# e-Tapperhandpiece.net
KiCad netlist of a schematic drawn in EAGLE
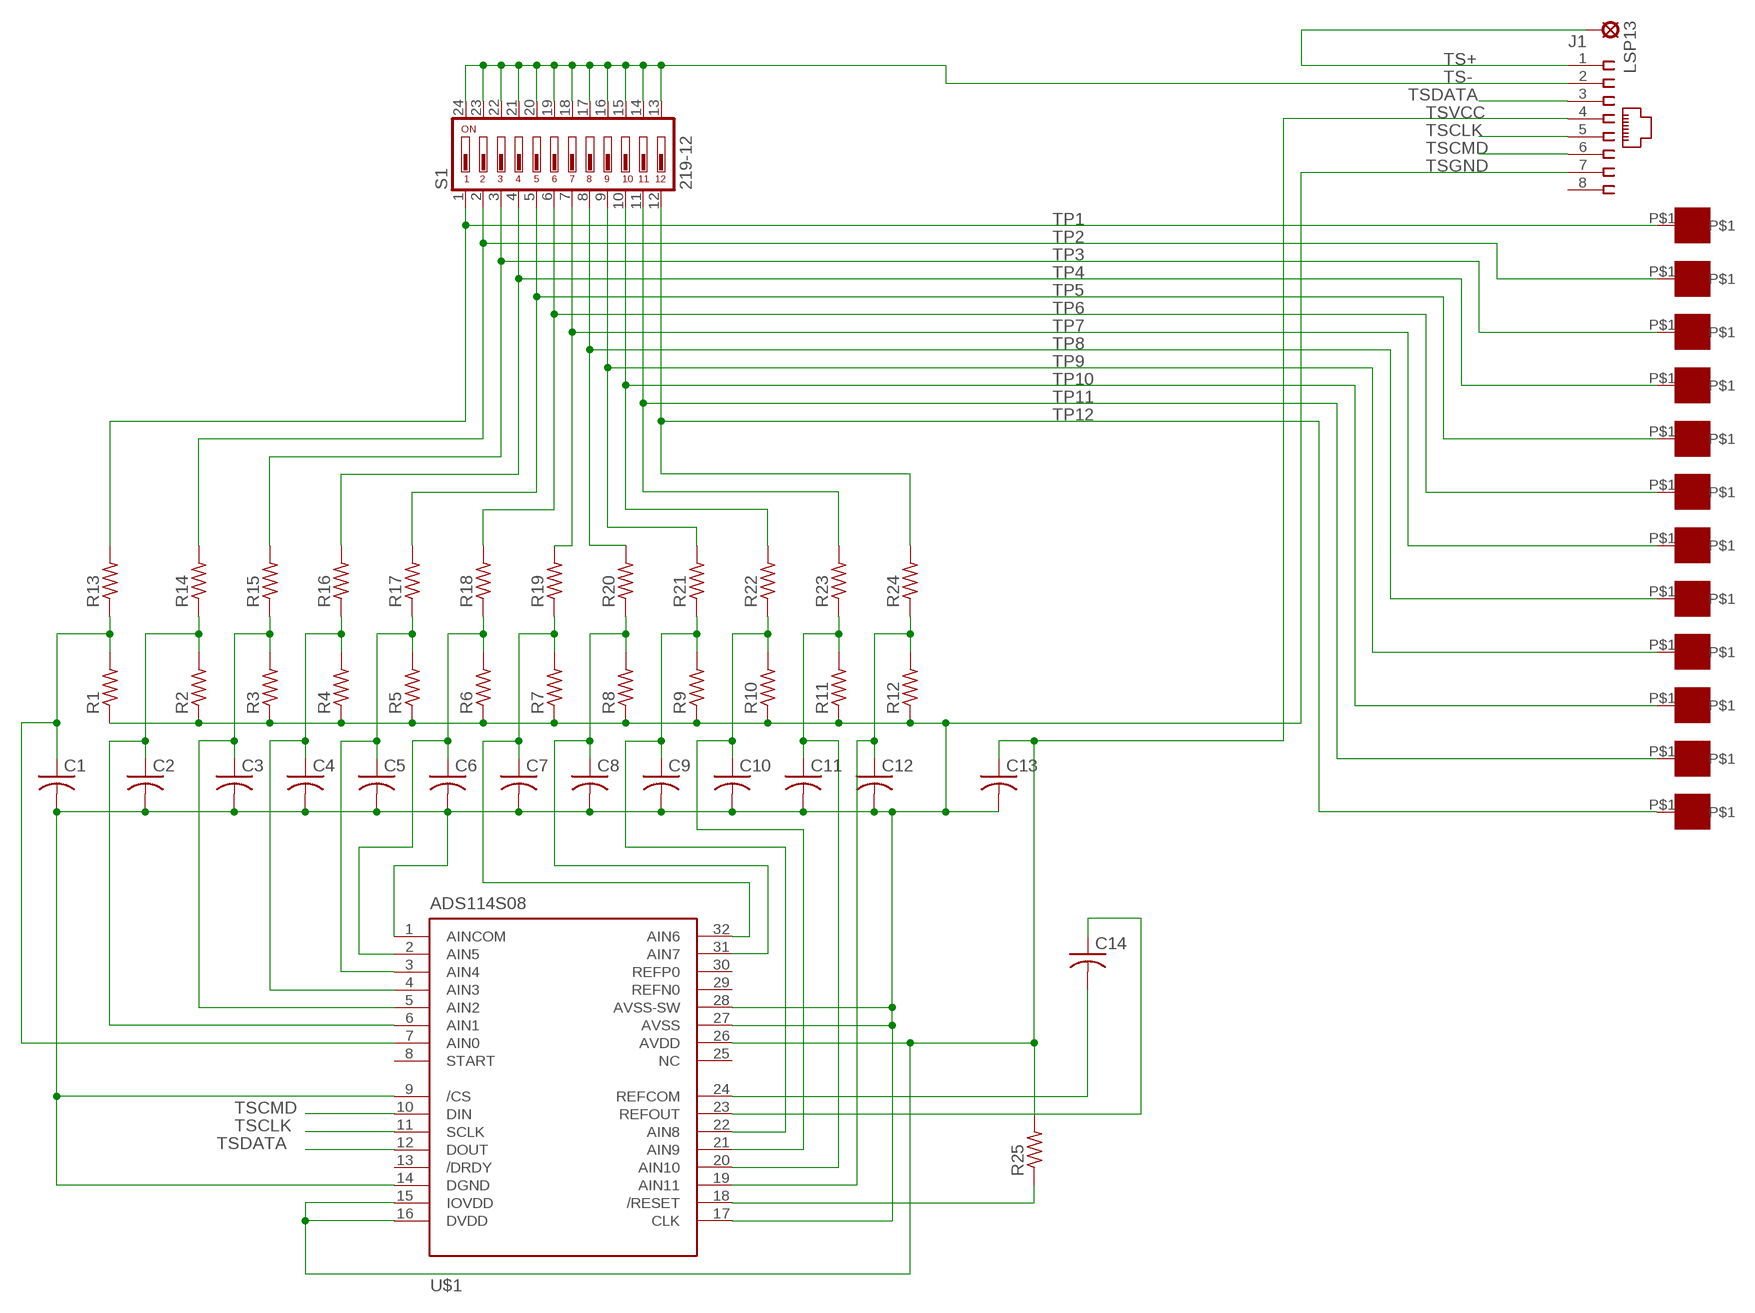
[diagram p0: schematic, sheet 1]

(export (version "E")
  (design (tool "Eeschema 10.0.6"))
  (components
    (comp (ref "C1")
      (value "C-USC0805")
      (footprint "eagle-import:C0805")
      (libsource (lib "eagle-import") (part "C-USC0805"))
    )
    (comp (ref "C2")
      (value "C-USC0805")
      (footprint "eagle-import:C0805")
      (libsource (lib "eagle-import") (part "C-USC0805"))
    )
    (comp (ref "C3")
      (value "C-USC0805")
      (footprint "eagle-import:C0805")
      (libsource (lib "eagle-import") (part "C-USC0805"))
    )
    (comp (ref "C4")
      (value "C-USC0805")
      (footprint "eagle-import:C0805")
      (libsource (lib "eagle-import") (part "C-USC0805"))
    )
    (comp (ref "C5")
      (value "C-USC0805")
      (footprint "eagle-import:C0805")
      (libsource (lib "eagle-import") (part "C-USC0805"))
    )
    (comp (ref "C6")
      (value "C-USC0805")
      (footprint "eagle-import:C0805")
      (libsource (lib "eagle-import") (part "C-USC0805"))
    )
    (comp (ref "C7")
      (value "C-USC0805")
      (footprint "eagle-import:C0805")
      (libsource (lib "eagle-import") (part "C-USC0805"))
    )
    (comp (ref "C8")
      (value "C-USC0805")
      (footprint "eagle-import:C0805")
      (libsource (lib "eagle-import") (part "C-USC0805"))
    )
    (comp (ref "C9")
      (value "C-USC0805")
      (footprint "eagle-import:C0805")
      (libsource (lib "eagle-import") (part "C-USC0805"))
    )
    (comp (ref "C10")
      (value "C-USC0805")
      (footprint "eagle-import:C0805")
      (libsource (lib "eagle-import") (part "C-USC0805"))
    )
    (comp (ref "C11")
      (value "C-USC0805")
      (footprint "eagle-import:C0805")
      (libsource (lib "eagle-import") (part "C-USC0805"))
    )
    (comp (ref "C12")
      (value "C-USC0805")
      (footprint "eagle-import:C0805")
      (libsource (lib "eagle-import") (part "C-USC0805"))
    )
    (comp (ref "C13")
      (value "C-USC0805")
      (footprint "eagle-import:C0805")
      (libsource (lib "eagle-import") (part "C-USC0805"))
    )
    (comp (ref "C14")
      (value "C-USC0805")
      (footprint "eagle-import:C0805")
      (libsource (lib "eagle-import") (part "C-USC0805"))
    )
    (comp (ref "J1")
      (value "215877-4")
      (footprint "eagle-import:215877-4")
      (libsource (lib "eagle-import") (part "215877-4"))
    )
    (comp (ref "LSP13")
      (value "SE11")
      (footprint "eagle-import:SE11")
      (libsource (lib "eagle-import") (part "SE11"))
    )
    (comp (ref "R1")
      (value "R-US_R0402")
      (footprint "eagle-import:R0402")
      (libsource (lib "eagle-import") (part "R-US_R0402"))
    )
    (comp (ref "R2")
      (value "R-US_R0402")
      (footprint "eagle-import:R0402")
      (libsource (lib "eagle-import") (part "R-US_R0402"))
    )
    (comp (ref "R3")
      (value "R-US_R0402")
      (footprint "eagle-import:R0402")
      (libsource (lib "eagle-import") (part "R-US_R0402"))
    )
    (comp (ref "R4")
      (value "R-US_R0402")
      (footprint "eagle-import:R0402")
      (libsource (lib "eagle-import") (part "R-US_R0402"))
    )
    (comp (ref "R5")
      (value "R-US_R0402")
      (footprint "eagle-import:R0402")
      (libsource (lib "eagle-import") (part "R-US_R0402"))
    )
    (comp (ref "R6")
      (value "R-US_R0402")
      (footprint "eagle-import:R0402")
      (libsource (lib "eagle-import") (part "R-US_R0402"))
    )
    (comp (ref "R7")
      (value "R-US_R0402")
      (footprint "eagle-import:R0402")
      (libsource (lib "eagle-import") (part "R-US_R0402"))
    )
    (comp (ref "R8")
      (value "R-US_R0402")
      (footprint "eagle-import:R0402")
      (libsource (lib "eagle-import") (part "R-US_R0402"))
    )
    (comp (ref "R9")
      (value "R-US_R0402")
      (footprint "eagle-import:R0402")
      (libsource (lib "eagle-import") (part "R-US_R0402"))
    )
    (comp (ref "R10")
      (value "R-US_R0402")
      (footprint "eagle-import:R0402")
      (libsource (lib "eagle-import") (part "R-US_R0402"))
    )
    (comp (ref "R11")
      (value "R-US_R0402")
      (footprint "eagle-import:R0402")
      (libsource (lib "eagle-import") (part "R-US_R0402"))
    )
    (comp (ref "R12")
      (value "R-US_R0402")
      (footprint "eagle-import:R0402")
      (libsource (lib "eagle-import") (part "R-US_R0402"))
    )
    (comp (ref "R13")
      (value "R-US_R0402")
      (footprint "eagle-import:R0402")
      (libsource (lib "eagle-import") (part "R-US_R0402"))
    )
    (comp (ref "R14")
      (value "R-US_R0402")
      (footprint "eagle-import:R0402")
      (libsource (lib "eagle-import") (part "R-US_R0402"))
    )
    (comp (ref "R15")
      (value "R-US_R0402")
      (footprint "eagle-import:R0402")
      (libsource (lib "eagle-import") (part "R-US_R0402"))
    )
    (comp (ref "R16")
      (value "R-US_R0402")
      (footprint "eagle-import:R0402")
      (libsource (lib "eagle-import") (part "R-US_R0402"))
    )
    (comp (ref "R17")
      (value "R-US_R0402")
      (footprint "eagle-import:R0402")
      (libsource (lib "eagle-import") (part "R-US_R0402"))
    )
    (comp (ref "R18")
      (value "R-US_R0402")
      (footprint "eagle-import:R0402")
      (libsource (lib "eagle-import") (part "R-US_R0402"))
    )
    (comp (ref "R19")
      (value "R-US_R0402")
      (footprint "eagle-import:R0402")
      (libsource (lib "eagle-import") (part "R-US_R0402"))
    )
    (comp (ref "R20")
      (value "R-US_R0402")
      (footprint "eagle-import:R0402")
      (libsource (lib "eagle-import") (part "R-US_R0402"))
    )
    (comp (ref "R21")
      (value "R-US_R0402")
      (footprint "eagle-import:R0402")
      (libsource (lib "eagle-import") (part "R-US_R0402"))
    )
    (comp (ref "R22")
      (value "R-US_R0402")
      (footprint "eagle-import:R0402")
      (libsource (lib "eagle-import") (part "R-US_R0402"))
    )
    (comp (ref "R23")
      (value "R-US_R0402")
      (footprint "eagle-import:R0402")
      (libsource (lib "eagle-import") (part "R-US_R0402"))
    )
    (comp (ref "R24")
      (value "R-US_R0402")
      (footprint "eagle-import:R0402")
      (libsource (lib "eagle-import") (part "R-US_R0402"))
    )
    (comp (ref "R25")
      (value "R-US_R0402")
      (footprint "eagle-import:R0402")
      (libsource (lib "eagle-import") (part "R-US_R0402"))
    )
    (comp (ref "S1")
      (value "219-12")
      (footprint "eagle-import:CTS-219-12")
      (libsource (lib "eagle-import") (part "219-12"))
    )
    (comp (ref "TSP1")
      (value "ET1")
      (footprint "eagle-import:ET1")
      (libsource (lib "eagle-import") (part "ET1"))
    )
    (comp (ref "TSP2")
      (value "ET1")
      (footprint "eagle-import:ET1")
      (libsource (lib "eagle-import") (part "ET1"))
    )
    (comp (ref "TSP3")
      (value "ET1")
      (footprint "eagle-import:ET1")
      (libsource (lib "eagle-import") (part "ET1"))
    )
    (comp (ref "TSP4")
      (value "ET1")
      (footprint "eagle-import:ET1")
      (libsource (lib "eagle-import") (part "ET1"))
    )
    (comp (ref "TSP5")
      (value "ET1")
      (footprint "eagle-import:ET1")
      (libsource (lib "eagle-import") (part "ET1"))
    )
    (comp (ref "TSP6")
      (value "ET1")
      (footprint "eagle-import:ET1")
      (libsource (lib "eagle-import") (part "ET1"))
    )
    (comp (ref "TSP7")
      (value "ET1")
      (footprint "eagle-import:ET1")
      (libsource (lib "eagle-import") (part "ET1"))
    )
    (comp (ref "TSP8")
      (value "ET1")
      (footprint "eagle-import:ET1")
      (libsource (lib "eagle-import") (part "ET1"))
    )
    (comp (ref "TSP9")
      (value "ET1")
      (footprint "eagle-import:ET1")
      (libsource (lib "eagle-import") (part "ET1"))
    )
    (comp (ref "TSP10")
      (value "ET1")
      (footprint "eagle-import:ET1")
      (libsource (lib "eagle-import") (part "ET1"))
    )
    (comp (ref "TSP11")
      (value "ET1")
      (footprint "eagle-import:ET1")
      (libsource (lib "eagle-import") (part "ET1"))
    )
    (comp (ref "TSP12")
      (value "ET1")
      (footprint "eagle-import:ET1")
      (libsource (lib "eagle-import") (part "ET1"))
    )
    (comp (ref "U$1")
      (value "ADS114S08")
      (footprint "eagle-import:TQFP32-08")
      (libsource (lib "eagle-import") (part "ADS114S08"))
    )
  )
  (nets
    (net (code "1") (name "/TP1") (class "Default")
      (node (ref "R13") (pin "2") (pinfunction "2_2") (pintype "passive"))
      (node (ref "S1") (pin "1") (pinfunction "1_1") (pintype "passive"))
      (node (ref "TSP1") (pin "P$1") (pinfunction "P$1_P$1") (pintype "bidirectional"))
    )
    (net (code "2") (name "/TP2") (class "Default")
      (node (ref "R14") (pin "2") (pinfunction "2_2") (pintype "passive"))
      (node (ref "S1") (pin "2") (pinfunction "2_2") (pintype "passive"))
      (node (ref "TSP2") (pin "P$1") (pinfunction "P$1_P$1") (pintype "bidirectional"))
    )
    (net (code "3") (name "/TP3") (class "Default")
      (node (ref "R15") (pin "2") (pinfunction "2_2") (pintype "passive"))
      (node (ref "S1") (pin "3") (pinfunction "3_3") (pintype "passive"))
      (node (ref "TSP3") (pin "P$1") (pinfunction "P$1_P$1") (pintype "bidirectional"))
    )
    (net (code "4") (name "/TP4") (class "Default")
      (node (ref "R16") (pin "2") (pinfunction "2_2") (pintype "passive"))
      (node (ref "S1") (pin "4") (pinfunction "4_4") (pintype "passive"))
      (node (ref "TSP4") (pin "P$1") (pinfunction "P$1_P$1") (pintype "bidirectional"))
    )
    (net (code "5") (name "/TP5") (class "Default")
      (node (ref "R17") (pin "2") (pinfunction "2_2") (pintype "passive"))
      (node (ref "S1") (pin "5") (pinfunction "5_5") (pintype "passive"))
      (node (ref "TSP5") (pin "P$1") (pinfunction "P$1_P$1") (pintype "bidirectional"))
    )
    (net (code "6") (name "/TP6") (class "Default")
      (node (ref "R18") (pin "2") (pinfunction "2_2") (pintype "passive"))
      (node (ref "S1") (pin "6") (pinfunction "6_6") (pintype "passive"))
      (node (ref "TSP6") (pin "P$1") (pinfunction "P$1_P$1") (pintype "bidirectional"))
    )
    (net (code "7") (name "/TP7") (class "Default")
      (node (ref "R19") (pin "2") (pinfunction "2_2") (pintype "passive"))
      (node (ref "S1") (pin "7") (pinfunction "7_7") (pintype "passive"))
      (node (ref "TSP7") (pin "P$1") (pinfunction "P$1_P$1") (pintype "bidirectional"))
    )
    (net (code "8") (name "/TP8") (class "Default")
      (node (ref "R20") (pin "2") (pinfunction "2_2") (pintype "passive"))
      (node (ref "S1") (pin "8") (pinfunction "8_8") (pintype "passive"))
      (node (ref "TSP8") (pin "P$1") (pinfunction "P$1_P$1") (pintype "bidirectional"))
    )
    (net (code "9") (name "/TP9") (class "Default")
      (node (ref "R21") (pin "2") (pinfunction "2_2") (pintype "passive"))
      (node (ref "S1") (pin "9") (pinfunction "9_9") (pintype "passive"))
      (node (ref "TSP9") (pin "P$1") (pinfunction "P$1_P$1") (pintype "bidirectional"))
    )
    (net (code "10") (name "/TP10") (class "Default")
      (node (ref "R22") (pin "2") (pinfunction "2_2") (pintype "passive"))
      (node (ref "S1") (pin "10") (pinfunction "10_10") (pintype "passive"))
      (node (ref "TSP10") (pin "P$1") (pinfunction "P$1_P$1") (pintype "bidirectional"))
    )
    (net (code "11") (name "/TP11") (class "Default")
      (node (ref "R23") (pin "2") (pinfunction "2_2") (pintype "passive"))
      (node (ref "S1") (pin "11") (pinfunction "11_11") (pintype "passive"))
      (node (ref "TSP11") (pin "P$1") (pinfunction "P$1_P$1") (pintype "bidirectional"))
    )
    (net (code "12") (name "/TP12") (class "Default")
      (node (ref "R24") (pin "2") (pinfunction "2_2") (pintype "passive"))
      (node (ref "S1") (pin "12") (pinfunction "12_12") (pintype "passive"))
      (node (ref "TSP12") (pin "P$1") (pinfunction "P$1_P$1") (pintype "bidirectional"))
    )
    (net (code "13") (name "/TS+") (class "Default")
      (node (ref "J1") (pin "1") (pinfunction "1_1") (pintype "passive"))
      (node (ref "LSP13") (pin "MP") (pinfunction "MP_MP") (pintype "passive"))
    )
    (net (code "14") (name "/TS-") (class "Default")
      (node (ref "J1") (pin "2") (pinfunction "2_2") (pintype "passive"))
      (node (ref "S1") (pin "13") (pinfunction "13_13") (pintype "passive"))
      (node (ref "S1") (pin "14") (pinfunction "14_14") (pintype "passive"))
      (node (ref "S1") (pin "15") (pinfunction "15_15") (pintype "passive"))
      (node (ref "S1") (pin "16") (pinfunction "16_16") (pintype "passive"))
      (node (ref "S1") (pin "17") (pinfunction "17_17") (pintype "passive"))
      (node (ref "S1") (pin "18") (pinfunction "18_18") (pintype "passive"))
      (node (ref "S1") (pin "19") (pinfunction "19_19") (pintype "passive"))
      (node (ref "S1") (pin "20") (pinfunction "20_20") (pintype "passive"))
      (node (ref "S1") (pin "21") (pinfunction "21_21") (pintype "passive"))
      (node (ref "S1") (pin "22") (pinfunction "22_22") (pintype "passive"))
      (node (ref "S1") (pin "23") (pinfunction "23_23") (pintype "passive"))
      (node (ref "S1") (pin "24") (pinfunction "24_24") (pintype "passive"))
    )
    (net (code "15") (name "/TSCLK") (class "Default")
      (node (ref "J1") (pin "5") (pinfunction "5_5") (pintype "passive"))
      (node (ref "U$1") (pin "11") (pinfunction "SCLK_11") (pintype "input"))
    )
    (net (code "16") (name "/TSCMD") (class "Default")
      (node (ref "J1") (pin "6") (pinfunction "6_6") (pintype "passive"))
      (node (ref "U$1") (pin "10") (pinfunction "DIN_10") (pintype "input"))
    )
    (net (code "17") (name "/TSDATA") (class "Default")
      (node (ref "J1") (pin "3") (pinfunction "3_3") (pintype "passive"))
      (node (ref "U$1") (pin "12") (pinfunction "DOUT_12") (pintype "output"))
    )
    (net (code "18") (name "/TSGND") (class "Default")
      (node (ref "C1") (pin "2") (pinfunction "2_2") (pintype "passive"))
      (node (ref "C10") (pin "2") (pinfunction "2_2") (pintype "passive"))
      (node (ref "C11") (pin "2") (pinfunction "2_2") (pintype "passive"))
      (node (ref "C12") (pin "2") (pinfunction "2_2") (pintype "passive"))
      (node (ref "C13") (pin "2") (pinfunction "2_2") (pintype "passive"))
      (node (ref "C2") (pin "2") (pinfunction "2_2") (pintype "passive"))
      (node (ref "C3") (pin "2") (pinfunction "2_2") (pintype "passive"))
      (node (ref "C4") (pin "2") (pinfunction "2_2") (pintype "passive"))
      (node (ref "C5") (pin "2") (pinfunction "2_2") (pintype "passive"))
      (node (ref "C6") (pin "2") (pinfunction "2_2") (pintype "passive"))
      (node (ref "C7") (pin "2") (pinfunction "2_2") (pintype "passive"))
      (node (ref "C8") (pin "2") (pinfunction "2_2") (pintype "passive"))
      (node (ref "C9") (pin "2") (pinfunction "2_2") (pintype "passive"))
      (node (ref "J1") (pin "7") (pinfunction "7_7") (pintype "passive"))
      (node (ref "R1") (pin "1") (pinfunction "1_1") (pintype "passive"))
      (node (ref "R10") (pin "1") (pinfunction "1_1") (pintype "passive"))
      (node (ref "R11") (pin "1") (pinfunction "1_1") (pintype "passive"))
      (node (ref "R12") (pin "1") (pinfunction "1_1") (pintype "passive"))
      (node (ref "R2") (pin "1") (pinfunction "1_1") (pintype "passive"))
      (node (ref "R3") (pin "1") (pinfunction "1_1") (pintype "passive"))
      (node (ref "R4") (pin "1") (pinfunction "1_1") (pintype "passive"))
      (node (ref "R5") (pin "1") (pinfunction "1_1") (pintype "passive"))
      (node (ref "R6") (pin "1") (pinfunction "1_1") (pintype "passive"))
      (node (ref "R7") (pin "1") (pinfunction "1_1") (pintype "passive"))
      (node (ref "R8") (pin "1") (pinfunction "1_1") (pintype "passive"))
      (node (ref "R9") (pin "1") (pinfunction "1_1") (pintype "passive"))
      (node (ref "U$1") (pin "1") (pinfunction "AINCOM_1") (pintype "bidirectional"))
      (node (ref "U$1") (pin "14") (pinfunction "DGND_14") (pintype "power_in"))
      (node (ref "U$1") (pin "17") (pinfunction "CLK_17") (pintype "input"))
      (node (ref "U$1") (pin "27") (pinfunction "AVSS_27") (pintype "power_in"))
      (node (ref "U$1") (pin "28") (pinfunction "AVSS-SW_28") (pintype "power_in"))
      (node (ref "U$1") (pin "9") (pinfunction "/CS_9") (pintype "input"))
    )
    (net (code "19") (name "/TSVCC") (class "Default")
      (node (ref "C13") (pin "1") (pinfunction "1_1") (pintype "passive"))
      (node (ref "J1") (pin "4") (pinfunction "4_4") (pintype "passive"))
      (node (ref "R25") (pin "2") (pinfunction "2_2") (pintype "passive"))
      (node (ref "U$1") (pin "15") (pinfunction "IOVDD_15") (pintype "power_in"))
      (node (ref "U$1") (pin "16") (pinfunction "DVDD_16") (pintype "power_in"))
      (node (ref "U$1") (pin "26") (pinfunction "AVDD_26") (pintype "power_in"))
    )
    (net (code "20") (name "Net-(U$1-AIN0)") (class "Default")
      (node (ref "C1") (pin "1") (pinfunction "1_1") (pintype "passive"))
      (node (ref "R1") (pin "2") (pinfunction "2_2") (pintype "passive"))
      (node (ref "R13") (pin "1") (pinfunction "1_1") (pintype "passive"))
      (node (ref "U$1") (pin "7") (pinfunction "AIN0_7") (pintype "bidirectional"))
    )
    (net (code "21") (name "Net-(U$1-AIN1)") (class "Default")
      (node (ref "C2") (pin "1") (pinfunction "1_1") (pintype "passive"))
      (node (ref "R14") (pin "1") (pinfunction "1_1") (pintype "passive"))
      (node (ref "R2") (pin "2") (pinfunction "2_2") (pintype "passive"))
      (node (ref "U$1") (pin "6") (pinfunction "AIN1_6") (pintype "bidirectional"))
    )
    (net (code "22") (name "Net-(U$1-AIN2)") (class "Default")
      (node (ref "C3") (pin "1") (pinfunction "1_1") (pintype "passive"))
      (node (ref "R15") (pin "1") (pinfunction "1_1") (pintype "passive"))
      (node (ref "R3") (pin "2") (pinfunction "2_2") (pintype "passive"))
      (node (ref "U$1") (pin "5") (pinfunction "AIN2_5") (pintype "bidirectional"))
    )
    (net (code "23") (name "Net-(U$1-AIN3)") (class "Default")
      (node (ref "C4") (pin "1") (pinfunction "1_1") (pintype "passive"))
      (node (ref "R16") (pin "1") (pinfunction "1_1") (pintype "passive"))
      (node (ref "R4") (pin "2") (pinfunction "2_2") (pintype "passive"))
      (node (ref "U$1") (pin "4") (pinfunction "AIN3_4") (pintype "power_in"))
    )
    (net (code "24") (name "Net-(U$1-AIN4)") (class "Default")
      (node (ref "C5") (pin "1") (pinfunction "1_1") (pintype "passive"))
      (node (ref "R17") (pin "1") (pinfunction "1_1") (pintype "passive"))
      (node (ref "R5") (pin "2") (pinfunction "2_2") (pintype "passive"))
      (node (ref "U$1") (pin "3") (pinfunction "AIN4_3") (pintype "bidirectional"))
    )
    (net (code "25") (name "Net-(U$1-AIN5)") (class "Default")
      (node (ref "C6") (pin "1") (pinfunction "1_1") (pintype "passive"))
      (node (ref "R18") (pin "1") (pinfunction "1_1") (pintype "passive"))
      (node (ref "R6") (pin "2") (pinfunction "2_2") (pintype "passive"))
      (node (ref "U$1") (pin "2") (pinfunction "AIN5_2") (pintype "bidirectional"))
    )
    (net (code "26") (name "Net-(U$1-AIN6)") (class "Default")
      (node (ref "C7") (pin "1") (pinfunction "1_1") (pintype "passive"))
      (node (ref "R19") (pin "1") (pinfunction "1_1") (pintype "passive"))
      (node (ref "R7") (pin "2") (pinfunction "2_2") (pintype "passive"))
      (node (ref "U$1") (pin "32") (pinfunction "AIN6_32") (pintype "input"))
    )
    (net (code "27") (name "Net-(U$1-AIN7)") (class "Default")
      (node (ref "C8") (pin "1") (pinfunction "1_1") (pintype "passive"))
      (node (ref "R20") (pin "1") (pinfunction "1_1") (pintype "passive"))
      (node (ref "R8") (pin "2") (pinfunction "2_2") (pintype "passive"))
      (node (ref "U$1") (pin "31") (pinfunction "AIN7_31") (pintype "input"))
    )
    (net (code "28") (name "Net-(U$1-AIN8)") (class "Default")
      (node (ref "C9") (pin "1") (pinfunction "1_1") (pintype "passive"))
      (node (ref "R21") (pin "1") (pinfunction "1_1") (pintype "passive"))
      (node (ref "R9") (pin "2") (pinfunction "2_2") (pintype "passive"))
      (node (ref "U$1") (pin "22") (pinfunction "AIN8_22") (pintype "bidirectional"))
    )
    (net (code "29") (name "Net-(U$1-AIN9)") (class "Default")
      (node (ref "C10") (pin "1") (pinfunction "1_1") (pintype "passive"))
      (node (ref "R10") (pin "2") (pinfunction "2_2") (pintype "passive"))
      (node (ref "R22") (pin "1") (pinfunction "1_1") (pintype "passive"))
      (node (ref "U$1") (pin "21") (pinfunction "AIN9_21") (pintype "bidirectional"))
    )
    (net (code "30") (name "Net-(U$1-AIN10)") (class "Default")
      (node (ref "C11") (pin "1") (pinfunction "1_1") (pintype "passive"))
      (node (ref "R11") (pin "2") (pinfunction "2_2") (pintype "passive"))
      (node (ref "R23") (pin "1") (pinfunction "1_1") (pintype "passive"))
      (node (ref "U$1") (pin "20") (pinfunction "AIN10_20") (pintype "bidirectional"))
    )
    (net (code "31") (name "Net-(U$1-AIN11)") (class "Default")
      (node (ref "C12") (pin "1") (pinfunction "1_1") (pintype "passive"))
      (node (ref "R12") (pin "2") (pinfunction "2_2") (pintype "passive"))
      (node (ref "R24") (pin "1") (pinfunction "1_1") (pintype "passive"))
      (node (ref "U$1") (pin "19") (pinfunction "AIN11_19") (pintype "bidirectional"))
    )
    (net (code "32") (name "Net-(U$1-REFCOM)") (class "Default")
      (node (ref "C14") (pin "2") (pinfunction "2_2") (pintype "passive"))
      (node (ref "U$1") (pin "24") (pinfunction "REFCOM_24") (pintype "power_in"))
    )
    (net (code "33") (name "Net-(U$1-REFOUT)") (class "Default")
      (node (ref "C14") (pin "1") (pinfunction "1_1") (pintype "passive"))
      (node (ref "U$1") (pin "23") (pinfunction "REFOUT_23") (pintype "power_in"))
    )
    (net (code "34") (name "Net-(U$1-{slash}RESET)") (class "Default")
      (node (ref "R25") (pin "1") (pinfunction "1_1") (pintype "passive"))
      (node (ref "U$1") (pin "18") (pinfunction "/RESET_18") (pintype "input"))
    )
    (net (code "35") (name "unconnected-(J1-Pad8)") (class "Default")
      (node (ref "J1") (pin "8") (pinfunction "8_8") (pintype "passive"))
    )
    (net (code "36") (name "unconnected-(U$1-NC-Pad25)") (class "Default")
      (node (ref "U$1") (pin "25") (pinfunction "NC_25") (pintype "passive"))
    )
    (net (code "37") (name "unconnected-(U$1-REFN0-Pad29)") (class "Default")
      (node (ref "U$1") (pin "29") (pinfunction "REFN0_29") (pintype "input"))
    )
    (net (code "38") (name "unconnected-(U$1-REFP0-Pad30)") (class "Default")
      (node (ref "U$1") (pin "30") (pinfunction "REFP0_30") (pintype "input"))
    )
    (net (code "39") (name "unconnected-(U$1-START-Pad8)") (class "Default")
      (node (ref "U$1") (pin "8") (pinfunction "START_8") (pintype "input"))
    )
    (net (code "40") (name "unconnected-(U$1-{slash}DRDY-Pad13)") (class "Default")
      (node (ref "U$1") (pin "13") (pinfunction "/DRDY_13") (pintype "output"))
    )
  )
)
